# VISUR-intR_a.net
KiCad netlist of a schematic drawn in Altium Designer
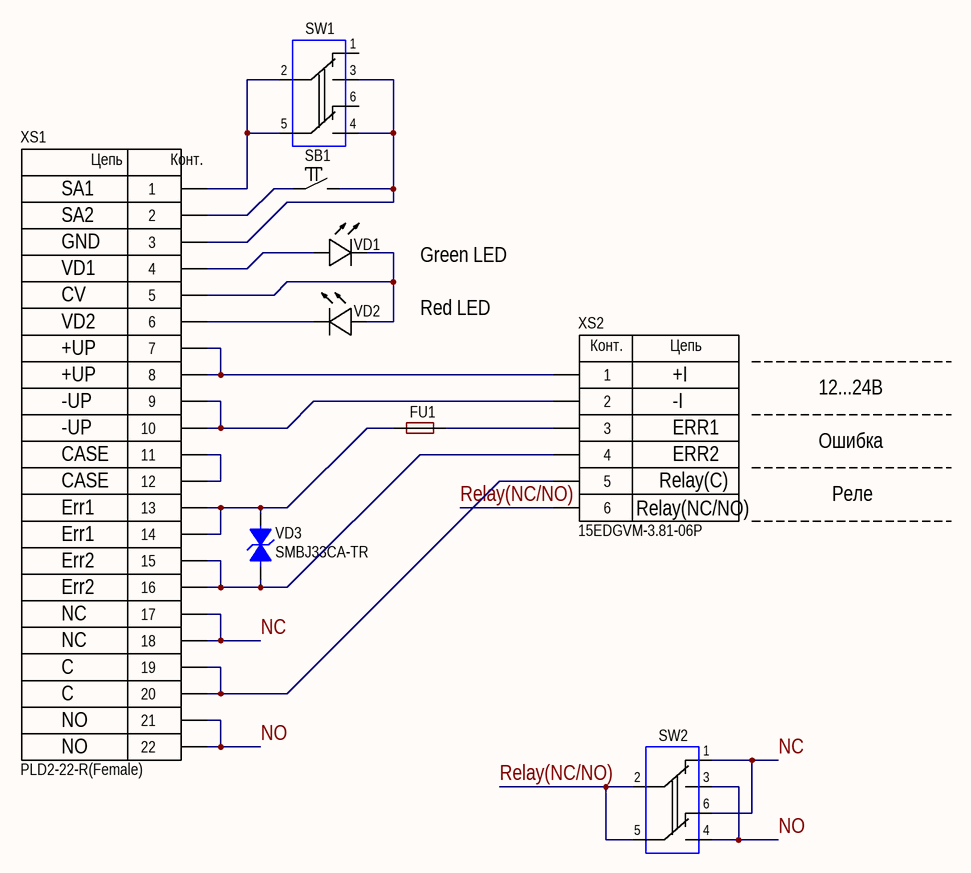
[diagram p0: VISUR-intR_a.SchDoc]

(export (version "E")
  (design (tool "Eeschema 10.0.6"))
  (components
    (comp (ref "FU1")
      (value "~")
      (footprint "FUSE: 1812")
      (fields
        (field (name "MANUFACTURER") "Littelfuse")
        (field (name "VALUEMANUFACTURERPARTNUMBER") "Electromechanics relay, 250VAC, , 5x20mm, ")
        (field (name "PARTNUMBER") "01110501Z")
      )
      (libsource (lib "electromechanics") (part "Fuse"))
    )
    (comp (ref "SB1")
      (value "~")
      (footprint "BUT: 6x6")
      (fields
        (field (name "MANUFACTURER") "TE Connectivity")
        (field (name "VALUEMANUFACTURERPARTNUMBER") "Tactile button, 6x6mm")
        (field (name "PARTNUMBER") "FSM2JSMAATR")
      )
      (libsource (lib "electromechanics") (part "Button_tactile"))
    )
    (comp (ref "SW1")
      (value "JS202011CQN")
      (footprint "JS202011CQN")
      (description "Переключатель")
      (fields
        (field (name "MANUFACTURER") "C&K Component")
        (field (name "REPLACEMENTPART1PARTNUMBER") "is-1390")
      )
      (libsource (lib "Switch") (part "JS202011SCQN"))
    )
    (comp (ref "SW2")
      (value "JS202011SCQN")
      (footprint "JS202011SCQN")
      (description "Переключатель")
      (fields
        (field (name "MANUFACTURER") "C&K Component")
        (field (name "REPLACEMENTPART1PARTNUMBER") "is-1390")
      )
      (libsource (lib "Switch") (part "JS202011SCQN"))
    )
    (comp (ref "VD1")
      (value "KM2520SURCK09")
      (footprint "KM2520SURCK09")
      (description "LED")
      (libsource (lib "Kingbright LED") (part "KM2520SURCK09"))
    )
    (comp (ref "VD2")
      (value "KM2520SURCK09")
      (footprint "KM2520SURCK09")
      (description "LED")
      (libsource (lib "Kingbright LED") (part "KM2520SURCK09"))
    )
    (comp (ref "VD3")
      (value "SMBJ33CA-TR")
      (footprint "DIODE: SMB")
      (libsource (lib "diode") (part "SMBJ10CA-TR"))
    )
    (comp (ref "XS1")
      (value "PLD2-22-R(Female)")
      (footprint "CON: PLD2-22-R(Female)")
      (libsource (lib "connector") (part "PLD2-22(Female)"))
    )
    (comp (ref "XS2")
      (value "15EDGVM-3.81-06P")
      (footprint "CON: 15EDGVM-3.81-06P")
      (libsource (lib "connector") (part "15EDGVM-3.81-06P"))
    )
  )
  (nets
    (net (code "1") (name "/NC") (class "Default")
      (node (ref "SW2") (pin "1") (pinfunction "1_1") (pintype "passive"))
      (node (ref "SW2") (pin "6") (pinfunction "6_6") (pintype "passive"))
      (node (ref "XS1") (pin "17") (pinfunction "17_17") (pintype "passive"))
      (node (ref "XS1") (pin "18") (pinfunction "18_18") (pintype "passive"))
    )
    (net (code "2") (name "/NO") (class "Default")
      (node (ref "SW2") (pin "3") (pinfunction "3_3") (pintype "passive"))
      (node (ref "SW2") (pin "4") (pinfunction "4_4") (pintype "passive"))
      (node (ref "XS1") (pin "21") (pinfunction "21_21") (pintype "passive"))
      (node (ref "XS1") (pin "22") (pinfunction "22_22") (pintype "passive"))
    )
    (net (code "3") (name "/Relay(NC{slash}NO)") (class "Default")
      (node (ref "SW2") (pin "2") (pinfunction "2_2") (pintype "passive"))
      (node (ref "SW2") (pin "5") (pinfunction "5_5") (pintype "passive"))
      (node (ref "XS2") (pin "6") (pinfunction "6_6") (pintype "passive"))
    )
    (net (code "4") (name "Net-(FU1-Pad1)") (class "Default")
      (node (ref "FU1") (pin "1") (pinfunction "1_1") (pintype "passive"))
      (node (ref "VD3") (pin "2") (pinfunction "2_2") (pintype "passive"))
      (node (ref "XS1") (pin "13") (pinfunction "13_13") (pintype "power_in"))
      (node (ref "XS1") (pin "14") (pinfunction "14_14") (pintype "power_in"))
    )
    (net (code "5") (name "Net-(FU1-Pad2)") (class "Default")
      (node (ref "FU1") (pin "2") (pinfunction "2_2") (pintype "passive"))
      (node (ref "XS2") (pin "3") (pinfunction "3_3") (pintype "passive"))
    )
    (net (code "6") (name "Net-(SB1-Pad1)") (class "Default")
      (node (ref "SB1") (pin "1") (pinfunction "1_1") (pintype "passive"))
      (node (ref "XS1") (pin "2") (pinfunction "2_2") (pintype "passive"))
    )
    (net (code "7") (name "Net-(SB1-Pad2)") (class "Default")
      (node (ref "SB1") (pin "2") (pinfunction "2_2") (pintype "passive"))
      (node (ref "SW1") (pin "3") (pinfunction "3_3") (pintype "passive"))
      (node (ref "SW1") (pin "4") (pinfunction "4_4") (pintype "passive"))
      (node (ref "XS1") (pin "3") (pinfunction "3_3") (pintype "power_in"))
    )
    (net (code "8") (name "Net-(SW1-Pad2)") (class "Default")
      (node (ref "SW1") (pin "2") (pinfunction "2_2") (pintype "passive"))
      (node (ref "SW1") (pin "5") (pinfunction "5_5") (pintype "passive"))
      (node (ref "XS1") (pin "1") (pinfunction "1_1") (pintype "passive"))
    )
    (net (code "9") (name "Net-(VD1-A)") (class "Default")
      (node (ref "VD1") (pin "1") (pinfunction "A_1") (pintype "passive"))
      (node (ref "XS1") (pin "4") (pinfunction "4_4") (pintype "power_in"))
    )
    (net (code "10") (name "Net-(VD1-K)") (class "Default")
      (node (ref "VD1") (pin "2") (pinfunction "K_2") (pintype "passive"))
      (node (ref "VD2") (pin "1") (pinfunction "A_1") (pintype "passive"))
      (node (ref "XS1") (pin "5") (pinfunction "5_5") (pintype "power_in"))
    )
    (net (code "11") (name "Net-(VD2-K)") (class "Default")
      (node (ref "VD2") (pin "2") (pinfunction "K_2") (pintype "passive"))
      (node (ref "XS1") (pin "6") (pinfunction "6_6") (pintype "power_in"))
    )
    (net (code "12") (name "Net-(VD3-Pad1)") (class "Default")
      (node (ref "VD3") (pin "1") (pinfunction "1_1") (pintype "passive"))
      (node (ref "XS1") (pin "15") (pinfunction "15_15") (pintype "passive"))
      (node (ref "XS1") (pin "16") (pinfunction "16_16") (pintype "passive"))
      (node (ref "XS2") (pin "4") (pinfunction "4_4") (pintype "passive"))
    )
    (net (code "13") (name "Net-(XS1-Pad7)") (class "Default")
      (node (ref "XS1") (pin "7") (pinfunction "7_7") (pintype "power_in"))
      (node (ref "XS1") (pin "8") (pinfunction "8_8") (pintype "power_in"))
      (node (ref "XS2") (pin "1") (pinfunction "1_1") (pintype "passive"))
    )
    (net (code "14") (name "Net-(XS1-Pad10)") (class "Default")
      (node (ref "XS1") (pin "10") (pinfunction "10_10") (pintype "power_in"))
      (node (ref "XS1") (pin "9") (pinfunction "9_9") (pintype "power_in"))
      (node (ref "XS2") (pin "2") (pinfunction "2_2") (pintype "passive"))
    )
    (net (code "15") (name "Net-(XS1-Pad11)") (class "Default")
      (node (ref "XS1") (pin "11") (pinfunction "11_11") (pintype "power_in"))
      (node (ref "XS1") (pin "12") (pinfunction "12_12") (pintype "power_in"))
    )
    (net (code "16") (name "Net-(XS1-Pad19)") (class "Default")
      (node (ref "XS1") (pin "19") (pinfunction "19_19") (pintype "passive"))
      (node (ref "XS1") (pin "20") (pinfunction "20_20") (pintype "passive"))
      (node (ref "XS2") (pin "5") (pinfunction "5_5") (pintype "passive"))
    )
    (net (code "17") (name "unconnected-(SW1-Pad1)") (class "Default")
      (node (ref "SW1") (pin "1") (pinfunction "1_1") (pintype "passive"))
    )
    (net (code "18") (name "unconnected-(SW1-Pad6)") (class "Default")
      (node (ref "SW1") (pin "6") (pinfunction "6_6") (pintype "passive"))
    )
  )
)
